# design.net
KiCad netlist of a schematic drawn in Altium Designer
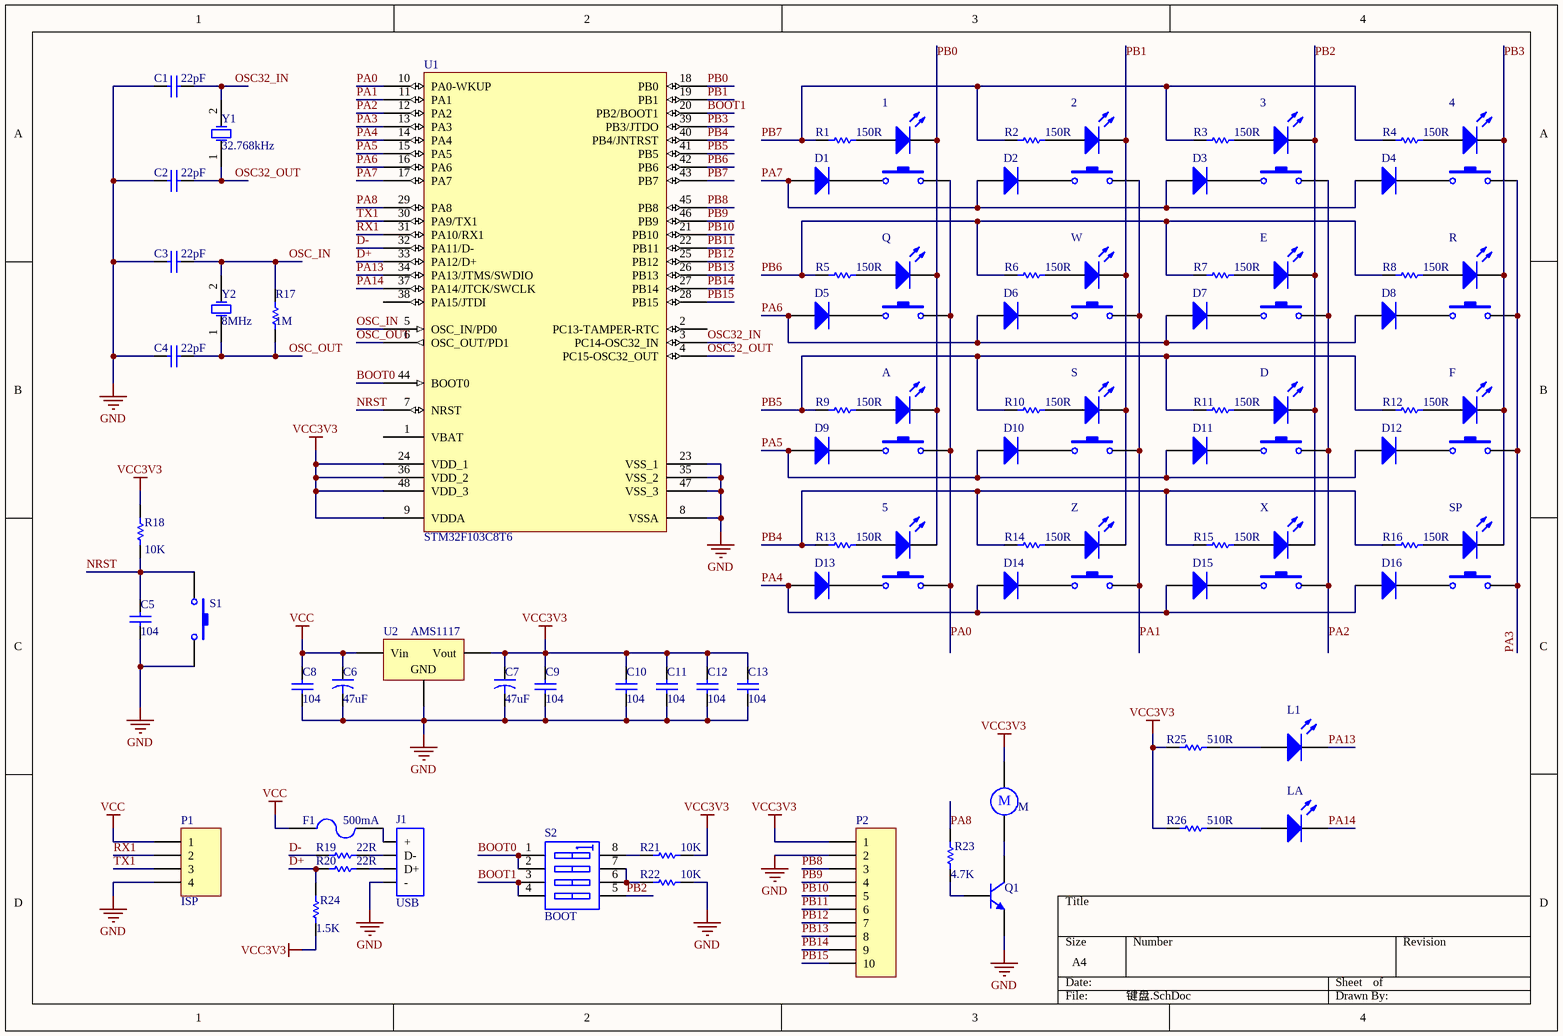
[diagram p0: 键盘.SchDoc]

(export (version "E")
  (design (tool "Eeschema 10.0.6"))
  (components
    (comp (ref "1") (value "MX5") (footprint "MX5F") (libsource (lib "lyq") (part "MX5")))
    (comp (ref "2") (value "MX5") (footprint "MX5F") (libsource (lib "lyq") (part "MX5")))
    (comp (ref "3") (value "MX5") (footprint "MX5F") (libsource (lib "lyq") (part "MX5")))
    (comp (ref "4") (value "MX5") (footprint "MX5F") (libsource (lib "lyq") (part "MX5")))
    (comp (ref "5") (value "MX5") (footprint "MX5F") (libsource (lib "lyq") (part "MX5")))
    (comp (ref "A") (value "MX5") (footprint "MX5F") (libsource (lib "lyq") (part "MX5")))
    (comp (ref "C1")
      (value "22pF")
      (footprint "0805")
      (description "Capacitor")
      (fields (field (name "Comment") "Cap") (field (name "PUBLISHER") "Altium Limited"))
      (libsource (lib "lyq") (part "Cap"))
    )
    (comp (ref "C2")
      (value "22pF")
      (footprint "0805")
      (description "Capacitor")
      (fields (field (name "Comment") "Cap") (field (name "PUBLISHER") "Altium Limited"))
      (libsource (lib "lyq") (part "Cap"))
    )
    (comp (ref "C3")
      (value "22pF")
      (footprint "0805")
      (description "Capacitor")
      (fields (field (name "Comment") "Cap") (field (name "PUBLISHER") "Altium Limited"))
      (libsource (lib "lyq") (part "Cap"))
    )
    (comp (ref "C4")
      (value "22pF")
      (footprint "0805")
      (description "Capacitor")
      (fields (field (name "Comment") "Cap") (field (name "PUBLISHER") "Altium Limited"))
      (libsource (lib "lyq") (part "Cap"))
    )
    (comp (ref "C5")
      (value "104")
      (footprint "0805")
      (description "Capacitor")
      (fields (field (name "Comment") "Cap") (field (name "PUBLISHER") "Altium Limited"))
      (libsource (lib "lyq") (part "Cap"))
    )
    (comp (ref "C6")
      (value "47uF")
      (footprint "B_3528")
      (description "Capacitor")
      (fields (field (name "Comment") "Cap2") (field (name "PUBLISHER") "Altium Limited"))
      (libsource (lib "lyq") (part "Cap2"))
    )
    (comp (ref "C7")
      (value "47uF")
      (footprint "B_3528")
      (description "Capacitor")
      (fields (field (name "Comment") "Cap2") (field (name "PUBLISHER") "Altium Limited"))
      (libsource (lib "lyq") (part "Cap2"))
    )
    (comp (ref "C8")
      (value "104")
      (footprint "0805")
      (description "Capacitor")
      (fields (field (name "Comment") "Cap") (field (name "PUBLISHER") "Altium Limited"))
      (libsource (lib "lyq") (part "Cap"))
    )
    (comp (ref "C9")
      (value "104")
      (footprint "0805")
      (description "Capacitor")
      (fields (field (name "Comment") "Cap") (field (name "PUBLISHER") "Altium Limited"))
      (libsource (lib "lyq") (part "Cap"))
    )
    (comp (ref "C10")
      (value "104")
      (footprint "0805")
      (description "Capacitor")
      (fields (field (name "Comment") "Cap") (field (name "PUBLISHER") "Altium Limited"))
      (libsource (lib "lyq") (part "Cap"))
    )
    (comp (ref "C11")
      (value "104")
      (footprint "0805")
      (description "Capacitor")
      (fields (field (name "Comment") "Cap") (field (name "PUBLISHER") "Altium Limited"))
      (libsource (lib "lyq") (part "Cap"))
    )
    (comp (ref "C12")
      (value "104")
      (footprint "0805")
      (description "Capacitor")
      (fields (field (name "Comment") "Cap") (field (name "PUBLISHER") "Altium Limited"))
      (libsource (lib "lyq") (part "Cap"))
    )
    (comp (ref "C13")
      (value "104")
      (footprint "0805")
      (description "Capacitor")
      (fields (field (name "Comment") "Cap") (field (name "PUBLISHER") "Altium Limited"))
      (libsource (lib "lyq") (part "Cap"))
    )
    (comp (ref "D") (value "MX5") (footprint "MX5F") (libsource (lib "lyq") (part "MX5")))
    (comp (ref "D1")
      (value "Diode")
      (footprint "贴片二极管")
      (description "Default Diode")
      (fields (field (name "PUBLISHER") "Altium Limited"))
      (libsource (lib "lyq") (part "Diode"))
    )
    (comp (ref "D2")
      (value "Diode")
      (footprint "贴片二极管")
      (description "Default Diode")
      (fields (field (name "PUBLISHER") "Altium Limited"))
      (libsource (lib "lyq") (part "Diode"))
    )
    (comp (ref "D3")
      (value "Diode")
      (footprint "贴片二极管")
      (description "Default Diode")
      (fields (field (name "PUBLISHER") "Altium Limited"))
      (libsource (lib "lyq") (part "Diode"))
    )
    (comp (ref "D4")
      (value "Diode")
      (footprint "贴片二极管")
      (description "Default Diode")
      (fields (field (name "PUBLISHER") "Altium Limited"))
      (libsource (lib "lyq") (part "Diode"))
    )
    (comp (ref "D5")
      (value "Diode")
      (footprint "贴片二极管")
      (description "Default Diode")
      (fields (field (name "PUBLISHER") "Altium Limited"))
      (libsource (lib "lyq") (part "Diode"))
    )
    (comp (ref "D6")
      (value "Diode")
      (footprint "贴片二极管")
      (description "Default Diode")
      (fields (field (name "PUBLISHER") "Altium Limited"))
      (libsource (lib "lyq") (part "Diode"))
    )
    (comp (ref "D7")
      (value "Diode")
      (footprint "贴片二极管")
      (description "Default Diode")
      (fields (field (name "PUBLISHER") "Altium Limited"))
      (libsource (lib "lyq") (part "Diode"))
    )
    (comp (ref "D8")
      (value "Diode")
      (footprint "贴片二极管")
      (description "Default Diode")
      (fields (field (name "PUBLISHER") "Altium Limited"))
      (libsource (lib "lyq") (part "Diode"))
    )
    (comp (ref "D9")
      (value "Diode")
      (footprint "贴片二极管")
      (description "Default Diode")
      (fields (field (name "PUBLISHER") "Altium Limited"))
      (libsource (lib "lyq") (part "Diode"))
    )
    (comp (ref "D10")
      (value "Diode")
      (footprint "贴片二极管")
      (description "Default Diode")
      (fields (field (name "PUBLISHER") "Altium Limited"))
      (libsource (lib "lyq") (part "Diode"))
    )
    (comp (ref "D11")
      (value "Diode")
      (footprint "贴片二极管")
      (description "Default Diode")
      (fields (field (name "PUBLISHER") "Altium Limited"))
      (libsource (lib "lyq") (part "Diode"))
    )
    (comp (ref "D12")
      (value "Diode")
      (footprint "贴片二极管")
      (description "Default Diode")
      (fields (field (name "PUBLISHER") "Altium Limited"))
      (libsource (lib "lyq") (part "Diode"))
    )
    (comp (ref "D13")
      (value "Diode")
      (footprint "贴片二极管")
      (description "Default Diode")
      (fields (field (name "PUBLISHER") "Altium Limited"))
      (libsource (lib "lyq") (part "Diode"))
    )
    (comp (ref "D14")
      (value "Diode")
      (footprint "贴片二极管")
      (description "Default Diode")
      (fields (field (name "PUBLISHER") "Altium Limited"))
      (libsource (lib "lyq") (part "Diode"))
    )
    (comp (ref "D15")
      (value "Diode")
      (footprint "贴片二极管")
      (description "Default Diode")
      (fields (field (name "PUBLISHER") "Altium Limited"))
      (libsource (lib "lyq") (part "Diode"))
    )
    (comp (ref "D16")
      (value "Diode")
      (footprint "贴片二极管")
      (description "Default Diode")
      (fields (field (name "PUBLISHER") "Altium Limited"))
      (libsource (lib "lyq") (part "Diode"))
    )
    (comp (ref "E") (value "MX5") (footprint "MX5F") (libsource (lib "lyq") (part "MX5")))
    (comp (ref "F") (value "MX5") (footprint "MX5F") (libsource (lib "lyq") (part "MX5")))
    (comp (ref "F1")
      (value "500mA")
      (footprint "1812")
      (description "Fuse")
      (fields (field (name "PUBLISHER") "Altium Limited"))
      (libsource (lib "lyq") (part "Fuse"))
    )
    (comp (ref "J1") (value "USB") (footprint "MiniUSB") (libsource (lib "lyq") (part "USB")))
    (comp (ref "L1")
      (value "LED")
      (footprint "0805")
      (description "Typical INFRARED GaAs LED")
      (fields (field (name "PUBLISHER") "Altium Limited"))
      (libsource (lib "lyq") (part "LED"))
    )
    (comp (ref "LA")
      (value "LED")
      (footprint "0805")
      (description "Typical INFRARED GaAs LED")
      (fields (field (name "PUBLISHER") "Altium Limited"))
      (libsource (lib "lyq") (part "LED"))
    )
    (comp (ref "M")
      (value "Motor")
      (footprint "Motor")
      (description "Motor, General Kind")
      (fields (field (name "PUBLISHER") "Altium Limited"))
      (libsource (lib "lyq") (part "Motor"))
    )
    (comp (ref "P1")
      (value "ISP")
      (footprint "PIN4")
      (description "Header, 4-Pin")
      (fields (field (name "PUBLISHER") "Altium Limited"))
      (libsource (lib "lyq") (part "PIN4"))
    )
    (comp (ref "P2")
      (value "PIN10")
      (footprint "PIN10")
      (description "Header, 10-Pin")
      (fields (field (name "PUBLISHER") "Altium Limited"))
      (libsource (lib "lyq") (part "PIN10"))
    )
    (comp (ref "Q") (value "MX5") (footprint "MX5F") (libsource (lib "lyq") (part "MX5")))
    (comp (ref "Q1")
      (value "NPN")
      (footprint "SOT-23_N")
      (description "NPN Bipolar Transistor")
      (fields (field (name "PUBLISHER") "Altium Limited"))
      (libsource (lib "lyq") (part "NPN"))
    )
    (comp (ref "R") (value "MX5") (footprint "MX5F") (libsource (lib "lyq") (part "MX5")))
    (comp (ref "R1")
      (value "150R")
      (footprint "0805")
      (description "Resistor")
      (fields (field (name "Comment") "Res") (field (name "PUBLISHER") "Altium Limited"))
      (libsource (lib "lyq") (part "Res"))
    )
    (comp (ref "R2")
      (value "150R")
      (footprint "0805")
      (description "Resistor")
      (fields (field (name "Comment") "Res") (field (name "PUBLISHER") "Altium Limited"))
      (libsource (lib "lyq") (part "Res"))
    )
    (comp (ref "R3")
      (value "150R")
      (footprint "0805")
      (description "Resistor")
      (fields (field (name "Comment") "Res") (field (name "PUBLISHER") "Altium Limited"))
      (libsource (lib "lyq") (part "Res"))
    )
    (comp (ref "R4")
      (value "150R")
      (footprint "0805")
      (description "Resistor")
      (fields (field (name "Comment") "Res") (field (name "PUBLISHER") "Altium Limited"))
      (libsource (lib "lyq") (part "Res"))
    )
    (comp (ref "R5")
      (value "150R")
      (footprint "0805")
      (description "Resistor")
      (fields (field (name "Comment") "Res") (field (name "PUBLISHER") "Altium Limited"))
      (libsource (lib "lyq") (part "Res"))
    )
    (comp (ref "R6")
      (value "150R")
      (footprint "0805")
      (description "Resistor")
      (fields (field (name "Comment") "Res") (field (name "PUBLISHER") "Altium Limited"))
      (libsource (lib "lyq") (part "Res"))
    )
    (comp (ref "R7")
      (value "150R")
      (footprint "0805")
      (description "Resistor")
      (fields (field (name "Comment") "Res") (field (name "PUBLISHER") "Altium Limited"))
      (libsource (lib "lyq") (part "Res"))
    )
    (comp (ref "R8")
      (value "150R")
      (footprint "0805")
      (description "Resistor")
      (fields (field (name "Comment") "Res") (field (name "PUBLISHER") "Altium Limited"))
      (libsource (lib "lyq") (part "Res"))
    )
    (comp (ref "R9")
      (value "150R")
      (footprint "0805")
      (description "Resistor")
      (fields (field (name "Comment") "Res") (field (name "PUBLISHER") "Altium Limited"))
      (libsource (lib "lyq") (part "Res"))
    )
    (comp (ref "R10")
      (value "150R")
      (footprint "0805")
      (description "Resistor")
      (fields (field (name "Comment") "Res") (field (name "PUBLISHER") "Altium Limited"))
      (libsource (lib "lyq") (part "Res"))
    )
    (comp (ref "R11")
      (value "150R")
      (footprint "0805")
      (description "Resistor")
      (fields (field (name "Comment") "Res") (field (name "PUBLISHER") "Altium Limited"))
      (libsource (lib "lyq") (part "Res"))
    )
    (comp (ref "R12")
      (value "150R")
      (footprint "0805")
      (description "Resistor")
      (fields (field (name "Comment") "Res") (field (name "PUBLISHER") "Altium Limited"))
      (libsource (lib "lyq") (part "Res"))
    )
    (comp (ref "R13")
      (value "150R")
      (footprint "0805")
      (description "Resistor")
      (fields (field (name "Comment") "Res") (field (name "PUBLISHER") "Altium Limited"))
      (libsource (lib "lyq") (part "Res"))
    )
    (comp (ref "R14")
      (value "150R")
      (footprint "0805")
      (description "Resistor")
      (fields (field (name "Comment") "Res") (field (name "PUBLISHER") "Altium Limited"))
      (libsource (lib "lyq") (part "Res"))
    )
    (comp (ref "R15")
      (value "150R")
      (footprint "0805")
      (description "Resistor")
      (fields (field (name "Comment") "Res") (field (name "PUBLISHER") "Altium Limited"))
      (libsource (lib "lyq") (part "Res"))
    )
    (comp (ref "R16")
      (value "150R")
      (footprint "0805")
      (description "Resistor")
      (fields (field (name "Comment") "Res") (field (name "PUBLISHER") "Altium Limited"))
      (libsource (lib "lyq") (part "Res"))
    )
    (comp (ref "R17")
      (value "1M")
      (footprint "0805")
      (description "Resistor")
      (fields (field (name "Comment") "Res") (field (name "PUBLISHER") "Altium Limited"))
      (libsource (lib "lyq") (part "Res"))
    )
    (comp (ref "R18")
      (value "10K")
      (footprint "0805")
      (description "Resistor")
      (fields (field (name "Comment") "Res") (field (name "PUBLISHER") "Altium Limited"))
      (libsource (lib "lyq") (part "Res"))
    )
    (comp (ref "R19")
      (value "22R")
      (footprint "0805")
      (description "Resistor")
      (fields (field (name "Comment") "Res") (field (name "PUBLISHER") "Altium Limited"))
      (libsource (lib "lyq") (part "Res"))
    )
    (comp (ref "R20")
      (value "22R")
      (footprint "0805")
      (description "Resistor")
      (fields (field (name "Comment") "Res") (field (name "PUBLISHER") "Altium Limited"))
      (libsource (lib "lyq") (part "Res"))
    )
    (comp (ref "R21")
      (value "10K")
      (footprint "0805")
      (description "Resistor")
      (fields (field (name "Comment") "Res") (field (name "PUBLISHER") "Altium Limited"))
      (libsource (lib "lyq") (part "Res"))
    )
    (comp (ref "R22")
      (value "10K")
      (footprint "0805")
      (description "Resistor")
      (fields (field (name "Comment") "Res") (field (name "PUBLISHER") "Altium Limited"))
      (libsource (lib "lyq") (part "Res"))
    )
    (comp (ref "R23")
      (value "4.7K")
      (footprint "0805")
      (description "Resistor")
      (fields (field (name "Comment") "Res") (field (name "PUBLISHER") "Altium Limited"))
      (libsource (lib "lyq") (part "Res"))
    )
    (comp (ref "R24")
      (value "1.5K")
      (footprint "0805")
      (description "Resistor")
      (fields (field (name "Comment") "Res") (field (name "PUBLISHER") "Altium Limited"))
      (libsource (lib "lyq") (part "Res"))
    )
    (comp (ref "R25")
      (value "510R")
      (footprint "0805")
      (description "Resistor")
      (fields (field (name "Comment") "Res") (field (name "PUBLISHER") "Altium Limited"))
      (libsource (lib "lyq") (part "Res"))
    )
    (comp (ref "R26")
      (value "510R")
      (footprint "0805")
      (description "Resistor")
      (fields (field (name "Comment") "Res") (field (name "PUBLISHER") "Altium Limited"))
      (libsource (lib "lyq") (part "Res"))
    )
    (comp (ref "S") (value "MX5") (footprint "MX5F") (libsource (lib "lyq") (part "MX5")))
    (comp (ref "S1")
      (value "SW-PB")
      (footprint "SW")
      (description "Switch")
      (fields (field (name "PUBLISHER") "Altium Limited"))
      (libsource (lib "lyq") (part "SW-PB"))
    )
    (comp (ref "S2")
      (value "BOOT")
      (footprint "SW-DIP-4")
      (description "DIP Switch, 4 Position, SPST")
      (fields (field (name "PUBLISHER") "Altium Limited"))
      (libsource (lib "lyq") (part "SW DIP-4"))
    )
    (comp (ref "SP") (value "MX5") (footprint "MX5F - 2") (libsource (lib "lyq") (part "MX5")))
    (comp (ref "U1")
      (value "STM32F103C8T6")
      (footprint "LQFP48_N")
      (description "STM32 ARM-based 32-bit MCU with 64 Kbytes Flash, 48-pin LQFP, Industrial Temperature")
      (fields (field (name "PUBLISHER") "Altium Limited"))
      (libsource (lib "lyq") (part "STM32F103C8T6"))
    )
    (comp (ref "U2")
      (value "AMS1117")
      (footprint "SOT223_N")
      (fields (field (name "PUBLISHER") "Altium Limited"))
      (libsource (lib "lyq") (part "AMS1117"))
    )
    (comp (ref "W") (value "MX5") (footprint "MX5F") (libsource (lib "lyq") (part "MX5")))
    (comp (ref "X") (value "MX5") (footprint "MX5F") (libsource (lib "lyq") (part "MX5")))
    (comp (ref "Y1")
      (value "32.768kHz")
      (footprint "RAD0.1")
      (description "Crystal Oscillator")
      (fields (field (name "PUBLISHER") "Altium Limited"))
      (libsource (lib "lyq") (part "XTAL"))
    )
    (comp (ref "Y2")
      (value "8MHz")
      (footprint "XTAL")
      (description "Crystal Oscillator")
      (fields (field (name "PUBLISHER") "Altium Limited"))
      (libsource (lib "lyq") (part "XTAL"))
    )
    (comp (ref "Z") (value "MX5") (footprint "MX5F") (libsource (lib "lyq") (part "MX5")))
  )
  (nets
    (net (code "1") (name "/BOOT0") (class "Default")
      (node (ref "S2") (pin "1") (pinfunction "A1_1") (pintype "passive"))
      (node (ref "S2") (pin "2") (pinfunction "A2_2") (pintype "passive"))
      (node (ref "U1") (pin "44") (pinfunction "BOOT0_44") (pintype "input"))
    )
    (net (code "2") (name "/BOOT1") (class "Default")
      (node (ref "S2") (pin "3") (pinfunction "A3_3") (pintype "passive"))
      (node (ref "S2") (pin "4") (pinfunction "A4_4") (pintype "passive"))
      (node (ref "U1") (pin "20") (pinfunction "PB2/BOOT1_20") (pintype "bidirectional"))
    )
    (net (code "3") (name "/D+") (class "Default")
      (node (ref "R20") (pin "1") (pinfunction "1_1") (pintype "passive"))
      (node (ref "R24") (pin "2") (pinfunction "2_2") (pintype "passive"))
      (node (ref "U1") (pin "33") (pinfunction "PA12/D+_33") (pintype "bidirectional"))
    )
    (net (code "4") (name "/D-") (class "Default")
      (node (ref "R19") (pin "1") (pinfunction "1_1") (pintype "passive"))
      (node (ref "U1") (pin "32") (pinfunction "PA11/D-_32") (pintype "bidirectional"))
    )
    (net (code "5") (name "/NRST") (class "Default")
      (node (ref "C5") (pin "2") (pinfunction "2_2") (pintype "passive"))
      (node (ref "R18") (pin "1") (pinfunction "1_1") (pintype "passive"))
      (node (ref "S1") (pin "1") (pinfunction "1_1") (pintype "passive"))
      (node (ref "U1") (pin "7") (pinfunction "NRST_7") (pintype "bidirectional"))
    )
    (net (code "6") (name "/OSC32_IN") (class "Default")
      (node (ref "C1") (pin "2") (pinfunction "2_2") (pintype "passive"))
      (node (ref "U1") (pin "3") (pinfunction "PC14-OSC32_IN_3") (pintype "bidirectional"))
      (node (ref "Y1") (pin "2") (pinfunction "OSC2_2") (pintype "passive"))
    )
    (net (code "7") (name "/OSC32_OUT") (class "Default")
      (node (ref "C2") (pin "2") (pinfunction "2_2") (pintype "passive"))
      (node (ref "U1") (pin "4") (pinfunction "PC15-OSC32_OUT_4") (pintype "bidirectional"))
      (node (ref "Y1") (pin "1") (pinfunction "OSC1_1") (pintype "passive"))
    )
    (net (code "8") (name "/OSC_IN") (class "Default")
      (node (ref "C3") (pin "2") (pinfunction "2_2") (pintype "passive"))
      (node (ref "R17") (pin "2") (pinfunction "2_2") (pintype "passive"))
      (node (ref "U1") (pin "5") (pinfunction "OSC_IN/PD0_5") (pintype "input"))
      (node (ref "Y2") (pin "2") (pinfunction "OSC2_2") (pintype "passive"))
    )
    (net (code "9") (name "/OSC_OUT") (class "Default")
      (node (ref "C4") (pin "2") (pinfunction "2_2") (pintype "passive"))
      (node (ref "R17") (pin "1") (pinfunction "1_1") (pintype "passive"))
      (node (ref "U1") (pin "6") (pinfunction "OSC_OUT/PD1_6") (pintype "output"))
      (node (ref "Y2") (pin "1") (pinfunction "OSC1_1") (pintype "passive"))
    )
    (net (code "10") (name "/PA0") (class "Default")
      (node (ref "1") (pin "2") (pinfunction "2_2") (pintype "passive"))
      (node (ref "5") (pin "2") (pinfunction "2_2") (pintype "passive"))
      (node (ref "A") (pin "2") (pinfunction "2_2") (pintype "passive"))
      (node (ref "Q") (pin "2") (pinfunction "2_2") (pintype "passive"))
      (node (ref "U1") (pin "10") (pinfunction "PA0-WKUP_10") (pintype "bidirectional"))
    )
    (net (code "11") (name "/PA1") (class "Default")
      (node (ref "2") (pin "2") (pinfunction "2_2") (pintype "passive"))
      (node (ref "S") (pin "2") (pinfunction "2_2") (pintype "passive"))
      (node (ref "U1") (pin "11") (pinfunction "PA1_11") (pintype "bidirectional"))
      (node (ref "W") (pin "2") (pinfunction "2_2") (pintype "passive"))
      (node (ref "Z") (pin "2") (pinfunction "2_2") (pintype "passive"))
    )
    (net (code "12") (name "/PA2") (class "Default")
      (node (ref "3") (pin "2") (pinfunction "2_2") (pintype "passive"))
      (node (ref "D") (pin "2") (pinfunction "2_2") (pintype "passive"))
      (node (ref "E") (pin "2") (pinfunction "2_2") (pintype "passive"))
      (node (ref "U1") (pin "12") (pinfunction "PA2_12") (pintype "bidirectional"))
      (node (ref "X") (pin "2") (pinfunction "2_2") (pintype "passive"))
    )
    (net (code "13") (name "/PA3") (class "Default")
      (node (ref "4") (pin "2") (pinfunction "2_2") (pintype "passive"))
      (node (ref "F") (pin "2") (pinfunction "2_2") (pintype "passive"))
      (node (ref "R") (pin "2") (pinfunction "2_2") (pintype "passive"))
      (node (ref "SP") (pin "2") (pinfunction "2_2") (pintype "passive"))
      (node (ref "U1") (pin "13") (pinfunction "PA3_13") (pintype "bidirectional"))
    )
    (net (code "14") (name "/PA4") (class "Default")
      (node (ref "D13") (pin "1") (pinfunction "A_1") (pintype "passive"))
      (node (ref "D14") (pin "1") (pinfunction "A_1") (pintype "passive"))
      (node (ref "D15") (pin "1") (pinfunction "A_1") (pintype "passive"))
      (node (ref "D16") (pin "1") (pinfunction "A_1") (pintype "passive"))
      (node (ref "U1") (pin "14") (pinfunction "PA4_14") (pintype "bidirectional"))
    )
    (net (code "15") (name "/PA5") (class "Default")
      (node (ref "D10") (pin "1") (pinfunction "A_1") (pintype "passive"))
      (node (ref "D11") (pin "1") (pinfunction "A_1") (pintype "passive"))
      (node (ref "D12") (pin "1") (pinfunction "A_1") (pintype "passive"))
      (node (ref "D9") (pin "1") (pinfunction "A_1") (pintype "passive"))
      (node (ref "U1") (pin "15") (pinfunction "PA5_15") (pintype "bidirectional"))
    )
    (net (code "16") (name "/PA6") (class "Default")
      (node (ref "D5") (pin "1") (pinfunction "A_1") (pintype "passive"))
      (node (ref "D6") (pin "1") (pinfunction "A_1") (pintype "passive"))
      (node (ref "D7") (pin "1") (pinfunction "A_1") (pintype "passive"))
      (node (ref "D8") (pin "1") (pinfunction "A_1") (pintype "passive"))
      (node (ref "U1") (pin "16") (pinfunction "PA6_16") (pintype "bidirectional"))
    )
    (net (code "17") (name "/PA7") (class "Default")
      (node (ref "D1") (pin "1") (pinfunction "A_1") (pintype "passive"))
      (node (ref "D2") (pin "1") (pinfunction "A_1") (pintype "passive"))
      (node (ref "D3") (pin "1") (pinfunction "A_1") (pintype "passive"))
      (node (ref "D4") (pin "1") (pinfunction "A_1") (pintype "passive"))
      (node (ref "U1") (pin "17") (pinfunction "PA7_17") (pintype "bidirectional"))
    )
    (net (code "18") (name "/PA8") (class "Default")
      (node (ref "R23") (pin "2") (pinfunction "2_2") (pintype "passive"))
      (node (ref "U1") (pin "29") (pinfunction "PA8_29") (pintype "bidirectional"))
    )
    (net (code "19") (name "/PA13") (class "Default")
      (node (ref "L1") (pin "2") (pinfunction "K_2") (pintype "passive"))
      (node (ref "U1") (pin "34") (pinfunction "PA13/JTMS/SWDIO_34") (pintype "bidirectional"))
    )
    (net (code "20") (name "/PA14") (class "Default")
      (node (ref "LA") (pin "2") (pinfunction "K_2") (pintype "passive"))
      (node (ref "U1") (pin "37") (pinfunction "PA14/JTCK/SWCLK_37") (pintype "bidirectional"))
    )
    (net (code "21") (name "/PB0") (class "Default")
      (node (ref "1") (pin "K") (pinfunction "K_K") (pintype "passive"))
      (node (ref "5") (pin "K") (pinfunction "K_K") (pintype "passive"))
      (node (ref "A") (pin "K") (pinfunction "K_K") (pintype "passive"))
      (node (ref "Q") (pin "K") (pinfunction "K_K") (pintype "passive"))
      (node (ref "U1") (pin "18") (pinfunction "PB0_18") (pintype "bidirectional"))
    )
    (net (code "22") (name "/PB1") (class "Default")
      (node (ref "2") (pin "K") (pinfunction "K_K") (pintype "passive"))
      (node (ref "S") (pin "K") (pinfunction "K_K") (pintype "passive"))
      (node (ref "U1") (pin "19") (pinfunction "PB1_19") (pintype "bidirectional"))
      (node (ref "W") (pin "K") (pinfunction "K_K") (pintype "passive"))
      (node (ref "Z") (pin "K") (pinfunction "K_K") (pintype "passive"))
    )
    (net (code "23") (name "/PB2") (class "Default")
      (node (ref "3") (pin "K") (pinfunction "K_K") (pintype "passive"))
      (node (ref "D") (pin "K") (pinfunction "K_K") (pintype "passive"))
      (node (ref "E") (pin "K") (pinfunction "K_K") (pintype "passive"))
      (node (ref "S2") (pin "5") (pinfunction "B4_5") (pintype "passive"))
      (node (ref "X") (pin "K") (pinfunction "K_K") (pintype "passive"))
    )
    (net (code "24") (name "/PB3") (class "Default")
      (node (ref "4") (pin "K") (pinfunction "K_K") (pintype "passive"))
      (node (ref "F") (pin "K") (pinfunction "K_K") (pintype "passive"))
      (node (ref "R") (pin "K") (pinfunction "K_K") (pintype "passive"))
      (node (ref "SP") (pin "K") (pinfunction "K_K") (pintype "passive"))
      (node (ref "U1") (pin "39") (pinfunction "PB3/JTDO_39") (pintype "bidirectional"))
    )
    (net (code "25") (name "/PB4") (class "Default")
      (node (ref "R13") (pin "1") (pinfunction "1_1") (pintype "passive"))
      (node (ref "R14") (pin "1") (pinfunction "1_1") (pintype "passive"))
      (node (ref "R15") (pin "1") (pinfunction "1_1") (pintype "passive"))
      (node (ref "R16") (pin "1") (pinfunction "1_1") (pintype "passive"))
      (node (ref "U1") (pin "40") (pinfunction "PB4/JNTRST_40") (pintype "bidirectional"))
    )
    (net (code "26") (name "/PB5") (class "Default")
      (node (ref "R10") (pin "1") (pinfunction "1_1") (pintype "passive"))
      (node (ref "R11") (pin "1") (pinfunction "1_1") (pintype "passive"))
      (node (ref "R12") (pin "1") (pinfunction "1_1") (pintype "passive"))
      (node (ref "R9") (pin "1") (pinfunction "1_1") (pintype "passive"))
      (node (ref "U1") (pin "41") (pinfunction "PB5_41") (pintype "bidirectional"))
    )
    (net (code "27") (name "/PB6") (class "Default")
      (node (ref "R5") (pin "1") (pinfunction "1_1") (pintype "passive"))
      (node (ref "R6") (pin "1") (pinfunction "1_1") (pintype "passive"))
      (node (ref "R7") (pin "1") (pinfunction "1_1") (pintype "passive"))
      (node (ref "R8") (pin "1") (pinfunction "1_1") (pintype "passive"))
      (node (ref "U1") (pin "42") (pinfunction "PB6_42") (pintype "bidirectional"))
    )
    (net (code "28") (name "/PB7") (class "Default")
      (node (ref "R1") (pin "1") (pinfunction "1_1") (pintype "passive"))
      (node (ref "R2") (pin "1") (pinfunction "1_1") (pintype "passive"))
      (node (ref "R3") (pin "1") (pinfunction "1_1") (pintype "passive"))
      (node (ref "R4") (pin "1") (pinfunction "1_1") (pintype "passive"))
      (node (ref "U1") (pin "43") (pinfunction "PB7_43") (pintype "bidirectional"))
    )
    (net (code "29") (name "/PB8") (class "Default")
      (node (ref "P2") (pin "3") (pinfunction "3_3") (pintype "passive"))
      (node (ref "U1") (pin "45") (pinfunction "PB8_45") (pintype "bidirectional"))
    )
    (net (code "30") (name "/PB9") (class "Default")
      (node (ref "P2") (pin "4") (pinfunction "4_4") (pintype "passive"))
      (node (ref "U1") (pin "46") (pinfunction "PB9_46") (pintype "bidirectional"))
    )
    (net (code "31") (name "/PB10") (class "Default")
      (node (ref "P2") (pin "5") (pinfunction "5_5") (pintype "passive"))
      (node (ref "U1") (pin "21") (pinfunction "PB10_21") (pintype "bidirectional"))
    )
    (net (code "32") (name "/PB11") (class "Default")
      (node (ref "P2") (pin "6") (pinfunction "6_6") (pintype "passive"))
      (node (ref "U1") (pin "22") (pinfunction "PB11_22") (pintype "bidirectional"))
    )
    (net (code "33") (name "/PB12") (class "Default")
      (node (ref "P2") (pin "7") (pinfunction "7_7") (pintype "passive"))
      (node (ref "U1") (pin "25") (pinfunction "PB12_25") (pintype "bidirectional"))
    )
    (net (code "34") (name "/PB13") (class "Default")
      (node (ref "P2") (pin "8") (pinfunction "8_8") (pintype "passive"))
      (node (ref "U1") (pin "26") (pinfunction "PB13_26") (pintype "bidirectional"))
    )
    (net (code "35") (name "/PB14") (class "Default")
      (node (ref "P2") (pin "9") (pinfunction "9_9") (pintype "passive"))
      (node (ref "U1") (pin "27") (pinfunction "PB14_27") (pintype "bidirectional"))
    )
    (net (code "36") (name "/PB15") (class "Default")
      (node (ref "P2") (pin "10") (pinfunction "10_10") (pintype "passive"))
      (node (ref "U1") (pin "28") (pinfunction "PB15_28") (pintype "bidirectional"))
    )
    (net (code "37") (name "/RX1") (class "Default")
      (node (ref "P1") (pin "2") (pinfunction "2_2") (pintype "passive"))
      (node (ref "U1") (pin "31") (pinfunction "PA10/RX1_31") (pintype "bidirectional"))
    )
    (net (code "38") (name "/TX1") (class "Default")
      (node (ref "P1") (pin "3") (pinfunction "3_3") (pintype "passive"))
      (node (ref "U1") (pin "30") (pinfunction "PA9/TX1_30") (pintype "bidirectional"))
    )
    (net (code "39") (name "GND") (class "Default")
      (node (ref "C1") (pin "1") (pinfunction "1_1") (pintype "passive"))
      (node (ref "C10") (pin "1") (pinfunction "1_1") (pintype "passive"))
      (node (ref "C11") (pin "1") (pinfunction "1_1") (pintype "passive"))
      (node (ref "C12") (pin "1") (pinfunction "1_1") (pintype "passive"))
      (node (ref "C13") (pin "1") (pinfunction "1_1") (pintype "passive"))
      (node (ref "C2") (pin "1") (pinfunction "1_1") (pintype "passive"))
      (node (ref "C3") (pin "1") (pinfunction "1_1") (pintype "passive"))
      (node (ref "C4") (pin "1") (pinfunction "1_1") (pintype "passive"))
      (node (ref "C5") (pin "1") (pinfunction "1_1") (pintype "passive"))
      (node (ref "C6") (pin "2") (pinfunction "2_2") (pintype "passive"))
      (node (ref "C7") (pin "2") (pinfunction "2_2") (pintype "passive"))
      (node (ref "C8") (pin "1") (pinfunction "1_1") (pintype "passive"))
      (node (ref "C9") (pin "1") (pinfunction "1_1") (pintype "passive"))
      (node (ref "J1") (pin "5") (pinfunction "-_5") (pintype "passive"))
      (node (ref "P1") (pin "4") (pinfunction "4_4") (pintype "passive"))
      (node (ref "P2") (pin "2") (pinfunction "2_2") (pintype "passive"))
      (node (ref "Q1") (pin "2") (pinfunction "E_2") (pintype "passive"))
      (node (ref "R22") (pin "1") (pinfunction "1_1") (pintype "passive"))
      (node (ref "S1") (pin "2") (pinfunction "2_2") (pintype "passive"))
      (node (ref "U1") (pin "23") (pinfunction "VSS_1_23") (pintype "power_in"))
      (node (ref "U1") (pin "35") (pinfunction "VSS_2_35") (pintype "power_in"))
      (node (ref "U1") (pin "47") (pinfunction "VSS_3_47") (pintype "power_in"))
      (node (ref "U1") (pin "8") (pinfunction "VSSA_8") (pintype "power_in"))
      (node (ref "U2") (pin "1") (pinfunction "GND_1") (pintype "passive"))
    )
    (net (code "40") (name "Net-(1-PadA)") (class "Default")
      (node (ref "1") (pin "A") (pinfunction "A_A") (pintype "passive"))
      (node (ref "R1") (pin "2") (pinfunction "2_2") (pintype "passive"))
    )
    (net (code "41") (name "Net-(2-PadA)") (class "Default")
      (node (ref "2") (pin "A") (pinfunction "A_A") (pintype "passive"))
      (node (ref "R2") (pin "2") (pinfunction "2_2") (pintype "passive"))
    )
    (net (code "42") (name "Net-(3-PadA)") (class "Default")
      (node (ref "3") (pin "A") (pinfunction "A_A") (pintype "passive"))
      (node (ref "R3") (pin "2") (pinfunction "2_2") (pintype "passive"))
    )
    (net (code "43") (name "Net-(4-PadA)") (class "Default")
      (node (ref "4") (pin "A") (pinfunction "A_A") (pintype "passive"))
      (node (ref "R4") (pin "2") (pinfunction "2_2") (pintype "passive"))
    )
    (net (code "44") (name "Net-(5-PadA)") (class "Default")
      (node (ref "5") (pin "A") (pinfunction "A_A") (pintype "passive"))
      (node (ref "R13") (pin "2") (pinfunction "2_2") (pintype "passive"))
    )
    (net (code "45") (name "Net-(A-PadA)") (class "Default")
      (node (ref "A") (pin "A") (pinfunction "A_A") (pintype "passive"))
      (node (ref "R9") (pin "2") (pinfunction "2_2") (pintype "passive"))
    )
    (net (code "46") (name "Net-(D-PadA)") (class "Default")
      (node (ref "D") (pin "A") (pinfunction "A_A") (pintype "passive"))
      (node (ref "R11") (pin "2") (pinfunction "2_2") (pintype "passive"))
    )
    (net (code "47") (name "Net-(D1-K)") (class "Default")
      (node (ref "1") (pin "1") (pinfunction "1_1") (pintype "passive"))
      (node (ref "D1") (pin "2") (pinfunction "K_2") (pintype "passive"))
    )
    (net (code "48") (name "Net-(D2-K)") (class "Default")
      (node (ref "2") (pin "1") (pinfunction "1_1") (pintype "passive"))
      (node (ref "D2") (pin "2") (pinfunction "K_2") (pintype "passive"))
    )
    (net (code "49") (name "Net-(D3-K)") (class "Default")
      (node (ref "3") (pin "1") (pinfunction "1_1") (pintype "passive"))
      (node (ref "D3") (pin "2") (pinfunction "K_2") (pintype "passive"))
    )
    (net (code "50") (name "Net-(D4-K)") (class "Default")
      (node (ref "4") (pin "1") (pinfunction "1_1") (pintype "passive"))
      (node (ref "D4") (pin "2") (pinfunction "K_2") (pintype "passive"))
    )
    (net (code "51") (name "Net-(D5-K)") (class "Default")
      (node (ref "D5") (pin "2") (pinfunction "K_2") (pintype "passive"))
      (node (ref "Q") (pin "1") (pinfunction "1_1") (pintype "passive"))
    )
    (net (code "52") (name "Net-(D6-K)") (class "Default")
      (node (ref "D6") (pin "2") (pinfunction "K_2") (pintype "passive"))
      (node (ref "W") (pin "1") (pinfunction "1_1") (pintype "passive"))
    )
    (net (code "53") (name "Net-(D7-K)") (class "Default")
      (node (ref "D7") (pin "2") (pinfunction "K_2") (pintype "passive"))
      (node (ref "E") (pin "1") (pinfunction "1_1") (pintype "passive"))
    )
    (net (code "54") (name "Net-(D8-K)") (class "Default")
      (node (ref "D8") (pin "2") (pinfunction "K_2") (pintype "passive"))
      (node (ref "R") (pin "1") (pinfunction "1_1") (pintype "passive"))
    )
    (net (code "55") (name "Net-(D9-K)") (class "Default")
      (node (ref "A") (pin "1") (pinfunction "1_1") (pintype "passive"))
      (node (ref "D9") (pin "2") (pinfunction "K_2") (pintype "passive"))
    )
    (net (code "56") (name "Net-(D10-K)") (class "Default")
      (node (ref "D10") (pin "2") (pinfunction "K_2") (pintype "passive"))
      (node (ref "S") (pin "1") (pinfunction "1_1") (pintype "passive"))
    )
    (net (code "57") (name "Net-(D11-K)") (class "Default")
      (node (ref "D") (pin "1") (pinfunction "1_1") (pintype "passive"))
      (node (ref "D11") (pin "2") (pinfunction "K_2") (pintype "passive"))
    )
    (net (code "58") (name "Net-(D12-K)") (class "Default")
      (node (ref "D12") (pin "2") (pinfunction "K_2") (pintype "passive"))
      (node (ref "F") (pin "1") (pinfunction "1_1") (pintype "passive"))
    )
    (net (code "59") (name "Net-(D13-K)") (class "Default")
      (node (ref "5") (pin "1") (pinfunction "1_1") (pintype "passive"))
      (node (ref "D13") (pin "2") (pinfunction "K_2") (pintype "passive"))
    )
    (net (code "60") (name "Net-(D14-K)") (class "Default")
      (node (ref "D14") (pin "2") (pinfunction "K_2") (pintype "passive"))
      (node (ref "Z") (pin "1") (pinfunction "1_1") (pintype "passive"))
    )
    (net (code "61") (name "Net-(D15-K)") (class "Default")
      (node (ref "D15") (pin "2") (pinfunction "K_2") (pintype "passive"))
      (node (ref "X") (pin "1") (pinfunction "1_1") (pintype "passive"))
    )
    (net (code "62") (name "Net-(D16-K)") (class "Default")
      (node (ref "D16") (pin "2") (pinfunction "K_2") (pintype "passive"))
      (node (ref "SP") (pin "1") (pinfunction "1_1") (pintype "passive"))
    )
    (net (code "63") (name "Net-(E-PadA)") (class "Default")
      (node (ref "E") (pin "A") (pinfunction "A_A") (pintype "passive"))
      (node (ref "R7") (pin "2") (pinfunction "2_2") (pintype "passive"))
    )
    (net (code "64") (name "Net-(F-PadA)") (class "Default")
      (node (ref "F") (pin "A") (pinfunction "A_A") (pintype "passive"))
      (node (ref "R12") (pin "2") (pinfunction "2_2") (pintype "passive"))
    )
    (net (code "65") (name "Net-(J1-+)") (class "Default")
      (node (ref "F1") (pin "2") (pinfunction "2_2") (pintype "passive"))
      (node (ref "J1") (pin "1") (pinfunction "+_1") (pintype "passive"))
    )
    (net (code "66") (name "Net-(J1-D+)") (class "Default")
      (node (ref "J1") (pin "3") (pinfunction "D+_3") (pintype "passive"))
      (node (ref "R20") (pin "2") (pinfunction "2_2") (pintype "passive"))
    )
    (net (code "67") (name "Net-(J1-D-)") (class "Default")
      (node (ref "J1") (pin "2") (pinfunction "D-_2") (pintype "passive"))
      (node (ref "R19") (pin "2") (pinfunction "2_2") (pintype "passive"))
    )
    (net (code "68") (name "Net-(L1-A)") (class "Default")
      (node (ref "L1") (pin "1") (pinfunction "A_1") (pintype "passive"))
      (node (ref "R25") (pin "2") (pinfunction "2_2") (pintype "passive"))
    )
    (net (code "69") (name "Net-(LA-A)") (class "Default")
      (node (ref "LA") (pin "1") (pinfunction "A_1") (pintype "passive"))
      (node (ref "R26") (pin "2") (pinfunction "2_2") (pintype "passive"))
    )
    (net (code "70") (name "Net-(Q-PadA)") (class "Default")
      (node (ref "Q") (pin "A") (pinfunction "A_A") (pintype "passive"))
      (node (ref "R5") (pin "2") (pinfunction "2_2") (pintype "passive"))
    )
    (net (code "71") (name "Net-(Q1-B)") (class "Default")
      (node (ref "Q1") (pin "1") (pinfunction "B_1") (pintype "passive"))
      (node (ref "R23") (pin "1") (pinfunction "1_1") (pintype "passive"))
    )
    (net (code "72") (name "Net-(Q1-C)") (class "Default")
      (node (ref "M") (pin "2") (pinfunction "2_2") (pintype "passive"))
      (node (ref "Q1") (pin "3") (pinfunction "C_3") (pintype "passive"))
    )
    (net (code "73") (name "Net-(R-PadA)") (class "Default")
      (node (ref "R") (pin "A") (pinfunction "A_A") (pintype "passive"))
      (node (ref "R8") (pin "2") (pinfunction "2_2") (pintype "passive"))
    )
    (net (code "74") (name "Net-(R6-Pad2)") (class "Default")
      (node (ref "R6") (pin "2") (pinfunction "2_2") (pintype "passive"))
      (node (ref "W") (pin "A") (pinfunction "A_A") (pintype "passive"))
    )
    (net (code "75") (name "Net-(R10-Pad2)") (class "Default")
      (node (ref "R10") (pin "2") (pinfunction "2_2") (pintype "passive"))
      (node (ref "S") (pin "A") (pinfunction "A_A") (pintype "passive"))
    )
    (net (code "76") (name "Net-(R14-Pad2)") (class "Default")
      (node (ref "R14") (pin "2") (pinfunction "2_2") (pintype "passive"))
      (node (ref "Z") (pin "A") (pinfunction "A_A") (pintype "passive"))
    )
    (net (code "77") (name "Net-(R15-Pad2)") (class "Default")
      (node (ref "R15") (pin "2") (pinfunction "2_2") (pintype "passive"))
      (node (ref "X") (pin "A") (pinfunction "A_A") (pintype "passive"))
    )
    (net (code "78") (name "Net-(R16-Pad2)") (class "Default")
      (node (ref "R16") (pin "2") (pinfunction "2_2") (pintype "passive"))
      (node (ref "SP") (pin "A") (pinfunction "A_A") (pintype "passive"))
    )
    (net (code "79") (name "Net-(S2-B1)") (class "Default")
      (node (ref "R21") (pin "2") (pinfunction "2_2") (pintype "passive"))
      (node (ref "S2") (pin "8") (pinfunction "B1_8") (pintype "passive"))
    )
    (net (code "80") (name "Net-(S2-B2)") (class "Default")
      (node (ref "R22") (pin "2") (pinfunction "2_2") (pintype "passive"))
      (node (ref "S2") (pin "6") (pinfunction "B3_6") (pintype "passive"))
      (node (ref "S2") (pin "7") (pinfunction "B2_7") (pintype "passive"))
    )
    (net (code "81") (name "VCC") (class "Default")
      (node (ref "C6") (pin "1") (pinfunction "1_1") (pintype "passive"))
      (node (ref "C8") (pin "2") (pinfunction "2_2") (pintype "passive"))
      (node (ref "F1") (pin "1") (pinfunction "1_1") (pintype "passive"))
      (node (ref "P1") (pin "1") (pinfunction "1_1") (pintype "passive"))
      (node (ref "U2") (pin "3") (pinfunction "Vin_3") (pintype "passive"))
    )
    (net (code "82") (name "VCC3V3") (class "Default")
      (node (ref "C10") (pin "2") (pinfunction "2_2") (pintype "passive"))
      (node (ref "C11") (pin "2") (pinfunction "2_2") (pintype "passive"))
      (node (ref "C12") (pin "2") (pinfunction "2_2") (pintype "passive"))
      (node (ref "C13") (pin "2") (pinfunction "2_2") (pintype "passive"))
      (node (ref "C7") (pin "1") (pinfunction "1_1") (pintype "passive"))
      (node (ref "C9") (pin "2") (pinfunction "2_2") (pintype "passive"))
      (node (ref "M") (pin "1") (pinfunction "1_1") (pintype "passive"))
      (node (ref "P2") (pin "1") (pinfunction "1_1") (pintype "passive"))
      (node (ref "R18") (pin "2") (pinfunction "2_2") (pintype "passive"))
      (node (ref "R21") (pin "1") (pinfunction "1_1") (pintype "passive"))
      (node (ref "R24") (pin "1") (pinfunction "1_1") (pintype "passive"))
      (node (ref "R25") (pin "1") (pinfunction "1_1") (pintype "passive"))
      (node (ref "R26") (pin "1") (pinfunction "1_1") (pintype "passive"))
      (node (ref "U1") (pin "24") (pinfunction "VDD_1_24") (pintype "power_in"))
      (node (ref "U1") (pin "36") (pinfunction "VDD_2_36") (pintype "power_in"))
      (node (ref "U1") (pin "48") (pinfunction "VDD_3_48") (pintype "power_in"))
      (node (ref "U1") (pin "9") (pinfunction "VDDA_9") (pintype "power_in"))
      (node (ref "U2") (pin "2") (pinfunction "Vout_2") (pintype "passive"))
    )
    (net (code "83") (name "unconnected-(U1-PA15{slash}JTDI-Pad38)") (class "Default")
      (node (ref "U1") (pin "38") (pinfunction "PA15/JTDI_38") (pintype "bidirectional"))
    )
    (net (code "84") (name "unconnected-(U1-PC13-TAMPER-RTC-Pad2)") (class "Default")
      (node (ref "U1") (pin "2") (pinfunction "PC13-TAMPER-RTC_2") (pintype "bidirectional"))
    )
    (net (code "85") (name "unconnected-(U1-VBAT-Pad1)") (class "Default")
      (node (ref "U1") (pin "1") (pinfunction "VBAT_1") (pintype "power_in"))
    )
  )
)
